# can2clusterV2.net
KiCad netlist of a schematic drawn in EasyEDA Pro
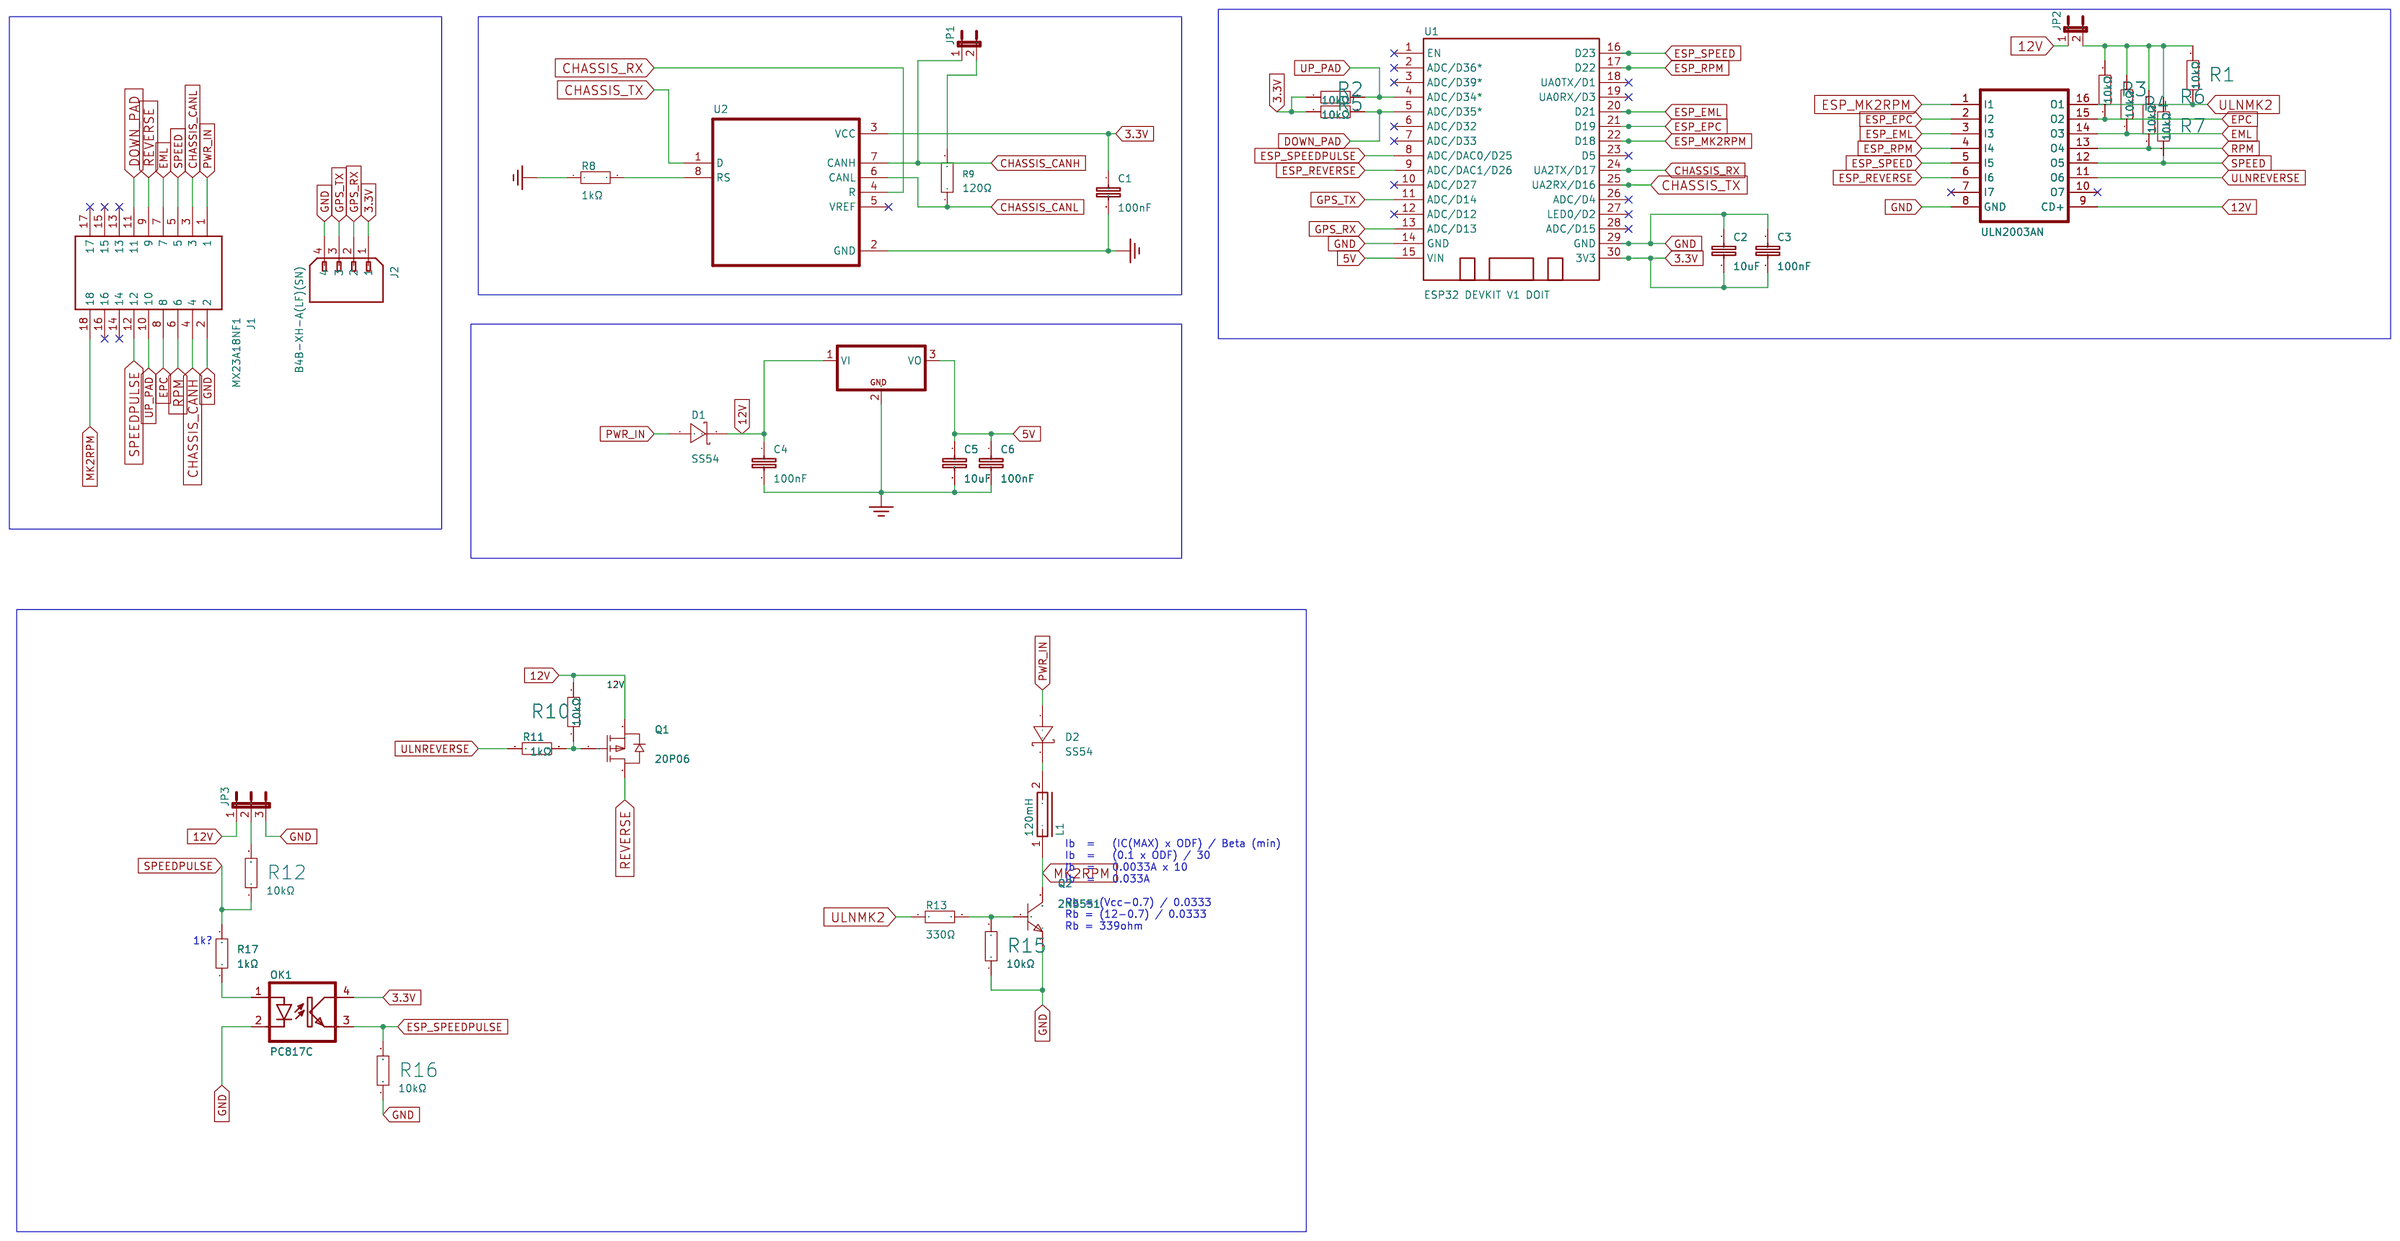
[diagram p0: schematic sheet]

(export (version "E")
  (design (tool "Eeschema 10.0.6"))
  (components
    (comp (ref "C1")
      (value "100nF")
      (footprint "easyedapro:C2.5-2")
      (description "Capacitance:100nF Tolerance:±10% Tolerance:±10% Voltage Rating:50V Temperature Coefficient:X7R")
      (fields
        (field (name "Manufacturer Part") "CC0603KRX7R9BB104")
        (field (name "Manufacturer") "YAGEO(国巨)")
      )
      (libsource (lib "easyedapro") (part "capacitor-wima_C_2.5/2"))
    )
    (comp (ref "C2")
      (value "10uF")
      (fields
        (field (name "Manufacturer Part") "CL21A106KAYNNNE")
        (field (name "Manufacturer") "SAMSUNG(三星)")
      )
      (libsource (lib "easyedapro") (part "capacitor-wima_C_2.5/2"))
    )
    (comp (ref "C3")
      (value "100nF")
      (footprint "easyedapro:C2.5-2")
      (description "Capacitance:100nF Tolerance:±10% Tolerance:±10% Voltage Rating:50V Temperature Coefficient:X7R")
      (fields
        (field (name "Manufacturer Part") "CC0603KRX7R9BB104")
        (field (name "Manufacturer") "YAGEO(国巨)")
      )
      (libsource (lib "easyedapro") (part "capacitor-wima_C_2.5/2"))
    )
    (comp (ref "C4")
      (value "100nF")
      (description "Capacitance:100nF Tolerance:±10% Tolerance:±10% Voltage Rating:50V Temperature Coefficient:X7R")
      (fields
        (field (name "Manufacturer Part") "CC0603KRX7R9BB104")
        (field (name "Manufacturer") "YAGEO(国巨)")
      )
      (libsource (lib "easyedapro") (part "capacitor-wima_C_2.5/2"))
    )
    (comp (ref "C5")
      (value "10uF")
      (fields
        (field (name "Manufacturer Part") "CL21A106KAYNNNE")
        (field (name "Manufacturer") "SAMSUNG(三星)")
      )
      (libsource (lib "easyedapro") (part "capacitor-wima_C_2.5/2"))
    )
    (comp (ref "C6")
      (value "100nF")
      (description "Capacitance:100nF Tolerance:±10% Tolerance:±10% Voltage Rating:50V Temperature Coefficient:X7R")
      (fields
        (field (name "Manufacturer Part") "CC0603KRX7R9BB104")
        (field (name "Manufacturer") "YAGEO(国巨)")
      )
      (libsource (lib "easyedapro") (part "capacitor-wima_C_2.5/2"))
    )
    (comp (ref "D1")
      (value "SS54")
      (footprint "easyedapro:SMA_L4.4-W2.8-LS5.4-R-RD")
      (fields (field (name "Manufacturer") "MDD(辰达半导体)"))
      (libsource (lib "easyedapro") (part "SS54_C22452"))
    )
    (comp (ref "D2")
      (value "SS54")
      (footprint "easyedapro:SMA_L4.4-W2.8-LS5.4-R-RD")
      (fields (field (name "Manufacturer") "MDD(辰达半导体)"))
      (libsource (lib "easyedapro") (part "SS54_C22452"))
    )
    (comp (ref "IC1")
      (value "ULN2003AN")
      (footprint "easyedapro:DIL16")
      (fields (field (name "Manufacturer") "HGSEMI(华冠)"))
      (libsource (lib "easyedapro") (part "ULN2003A_ULN2003A_N"))
    )
    (comp (ref "IC2")
      (value "L7805ABD2T-TR")
      (fields (field (name "Manufacturer") "ST(意法半导体)"))
      (libsource (lib "easyedapro") (part "linear_78*_TV"))
    )
    (comp (ref "J1")
      (value "MX23A18NF1")
      (footprint "easyedapro:MX23A18NF1")
      (fields (field (name "Manufacturer") "JAE(日本航空电子)"))
      (libsource (lib "easyedapro") (part "MX23A18NF1_MX23A18NF1_"))
    )
    (comp (ref "J2")
      (value "B4B-XH-A(LF)(SN)")
      (footprint "easyedapro:JST_B4B-XH-A(LF)(SN)")
      (fields (field (name "Manufacturer") "JST"))
      (libsource (lib "easyedapro") (part "B4B-XH-A_LF__SN__B4B-XH-A(LF)(SN)_"))
    )
    (comp (ref "JP1")
      (value "PZ254V-11-02P")
      (footprint "easyedapro:JP1")
      (fields (field (name "Manufacturer") "XFCN(兴飞)"))
      (libsource (lib "easyedapro") (part "jumper_JP1E_"))
    )
    (comp (ref "JP2")
      (value "PZ254V-11-02P")
      (footprint "easyedapro:JP1")
      (fields (field (name "Manufacturer") "XFCN(兴飞)"))
      (libsource (lib "easyedapro") (part "jumper_JP1E_"))
    )
    (comp (ref "JP3")
      (value "PZ254V-11-03P")
      (footprint "easyedapro:JP2")
      (fields (field (name "Manufacturer") "XFCN(兴飞)"))
      (libsource (lib "easyedapro") (part "jumper_JP2E_"))
    )
    (comp (ref "L1")
      (value "120mH")
      (footprint "easyedapro:DR125_3D")
      (fields (field (name "Manufacturer Part") "DR125-124-R") (field (name "Manufacturer") "EATON(伊顿)"))
      (libsource (lib "easyedapro") (part "DR125_DR125_"))
    )
    (comp (ref "OK1")
      (value "PC817C")
      (footprint "easyedapro:DIL04")
      (fields (field (name "Manufacturer") "GOODWORK(固得沃克)"))
      (libsource (lib "easyedapro") (part "optocoupler_PC817_"))
    )
    (comp (ref "Q1")
      (value "20P06")
      (footprint "easyedapro:TO-252-2_L6.6-W6.1-P4.57-LS9.9-BR-CW")
      (fields (field (name "Manufacturer") "HL(富海微)"))
      (libsource (lib "easyedapro") (part "20P06"))
    )
    (comp (ref "Q2")
      (value "2N5551")
      (footprint "easyedapro:SOT-23-3_L2.9-W1.4-P1.90-LS2.5-BR")
      (fields (field (name "Manufacturer") "RUILON(瑞隆源)"))
      (libsource (lib "easyedapro") (part "2N5551_C7529570"))
    )
    (comp (ref "R1")
      (value "10kΩ")
      (footprint "easyedapro:R0603")
      (fields
        (field (name "Manufacturer Part") "0603WAF1002T5E")
        (field (name "Manufacturer") "UNI-ROYAL(厚声)")
      )
      (libsource (lib "easyedapro") (part "0603WAF1002T5E"))
    )
    (comp (ref "R2")
      (value "10kΩ")
      (footprint "easyedapro:R0603")
      (fields
        (field (name "Manufacturer Part") "0603WAF1002T5E")
        (field (name "Manufacturer") "UNI-ROYAL(厚声)")
      )
      (libsource (lib "easyedapro") (part "0603WAF1002T5E"))
    )
    (comp (ref "R3")
      (value "10kΩ")
      (footprint "easyedapro:R0603")
      (fields
        (field (name "Manufacturer Part") "0603WAF1002T5E")
        (field (name "Manufacturer") "UNI-ROYAL(厚声)")
      )
      (libsource (lib "easyedapro") (part "0603WAF1002T5E"))
    )
    (comp (ref "R4")
      (value "10kΩ")
      (footprint "easyedapro:R0603")
      (fields
        (field (name "Manufacturer Part") "0603WAF1002T5E")
        (field (name "Manufacturer") "UNI-ROYAL(厚声)")
      )
      (libsource (lib "easyedapro") (part "0603WAF1002T5E"))
    )
    (comp (ref "R5")
      (value "10kΩ")
      (footprint "easyedapro:R0603")
      (fields
        (field (name "Manufacturer Part") "0603WAF1002T5E")
        (field (name "Manufacturer") "UNI-ROYAL(厚声)")
      )
      (libsource (lib "easyedapro") (part "0603WAF1002T5E"))
    )
    (comp (ref "R6")
      (value "10kΩ")
      (footprint "easyedapro:R0603")
      (fields
        (field (name "Manufacturer Part") "0603WAF1002T5E")
        (field (name "Manufacturer") "UNI-ROYAL(厚声)")
      )
      (libsource (lib "easyedapro") (part "0603WAF1002T5E"))
    )
    (comp (ref "R7")
      (value "10kΩ")
      (footprint "easyedapro:R0603")
      (fields
        (field (name "Manufacturer Part") "0603WAF1002T5E")
        (field (name "Manufacturer") "UNI-ROYAL(厚声)")
      )
      (libsource (lib "easyedapro") (part "0603WAF1002T5E"))
    )
    (comp (ref "R8")
      (value "1kΩ")
      (footprint "easyedapro:R0603")
      (fields
        (field (name "Manufacturer Part") "0603WAF1001T5E")
        (field (name "Manufacturer") "UNI-ROYAL(厚声)")
      )
      (libsource (lib "easyedapro") (part "0603WAF1001T5E"))
    )
    (comp (ref "R9")
      (value "120Ω")
      (footprint "easyedapro:R0603")
      (fields
        (field (name "Manufacturer Part") "0603WAF1200T5E")
        (field (name "Manufacturer") "UNI-ROYAL(厚声)")
      )
      (libsource (lib "easyedapro") (part "0603WAF1200T5E"))
    )
    (comp (ref "R10")
      (value "10kΩ")
      (footprint "easyedapro:R0603")
      (fields
        (field (name "Manufacturer Part") "0603WAF1002T5E")
        (field (name "Manufacturer") "UNI-ROYAL(厚声)")
      )
      (libsource (lib "easyedapro") (part "0603WAF1002T5E"))
    )
    (comp (ref "R11")
      (value "1kΩ")
      (footprint "easyedapro:R0603")
      (fields
        (field (name "Manufacturer Part") "0603WAF1001T5E")
        (field (name "Manufacturer") "UNI-ROYAL(厚声)")
      )
      (libsource (lib "easyedapro") (part "0603WAF1001T5E"))
    )
    (comp (ref "R12")
      (value "10kΩ")
      (footprint "easyedapro:R0603")
      (fields
        (field (name "Manufacturer Part") "0603WAF1002T5E")
        (field (name "Manufacturer") "UNI-ROYAL(厚声)")
      )
      (libsource (lib "easyedapro") (part "0603WAF1002T5E"))
    )
    (comp (ref "R13")
      (value "330Ω")
      (footprint "easyedapro:R0603")
      (fields
        (field (name "Manufacturer Part") "0603WAF3300T5E")
        (field (name "Manufacturer") "UNI-ROYAL(厚声)")
      )
      (libsource (lib "easyedapro") (part "0603WAF3300T5E"))
    )
    (comp (ref "R15")
      (value "10kΩ")
      (footprint "easyedapro:R0603")
      (fields
        (field (name "Manufacturer Part") "0603WAF1002T5E")
        (field (name "Manufacturer") "UNI-ROYAL(厚声)")
      )
      (libsource (lib "easyedapro") (part "0603WAF1002T5E"))
    )
    (comp (ref "R16")
      (value "10kΩ")
      (footprint "easyedapro:R0603")
      (fields
        (field (name "Manufacturer Part") "0603WAF1002T5E")
        (field (name "Manufacturer") "UNI-ROYAL(厚声)")
      )
      (libsource (lib "easyedapro") (part "0603WAF1002T5E"))
    )
    (comp (ref "R17")
      (value "1kΩ")
      (footprint "easyedapro:R0603")
      (fields
        (field (name "Manufacturer Part") "0603WAF1001T5E")
        (field (name "Manufacturer") "UNI-ROYAL(厚声)")
      )
      (libsource (lib "easyedapro") (part "0603WAF1001T5E"))
    )
    (comp (ref "U1")
      (value "ESP32 DEVKIT V1 DOIT")
      (footprint "easyedapro:DOIT-ESP32-DEVKIT-V1")
      (libsource (lib "easyedapro") (part "ESP32 DEVKIT V1 DOIT"))
    )
    (comp (ref "U2")
      (value "SN65HVD230DR")
      (footprint "easyedapro:SOIC127P599X175-8N")
      (fields (field (name "Manufacturer") "TI(德州仪器)"))
      (libsource (lib "easyedapro") (part "SN65HVD230DR_SN65HVD230DR_"))
    )
  )
  (nets
    (net (code "1") (name "3.3V") (class "Default")
      (node (ref "C1") (pin "1") (pinfunction "1_1") (pintype "unspecified"))
      (node (ref "C2") (pin "2") (pinfunction "2_2") (pintype "unspecified"))
      (node (ref "C3") (pin "2") (pinfunction "2_2") (pintype "unspecified"))
      (node (ref "J2") (pin "1") (pinfunction "1_1") (pintype "unspecified"))
      (node (ref "OK1") (pin "4") (pinfunction "COL_4") (pintype "unspecified"))
      (node (ref "R2") (pin "1") (pinfunction "1_1") (pintype "input"))
      (node (ref "R5") (pin "1") (pinfunction "1_1") (pintype "input"))
      (node (ref "U1") (pin "30") (pinfunction "3V3_30") (pintype "bidirectional"))
      (node (ref "U2") (pin "3") (pinfunction "VCC_3") (pintype "unspecified"))
    )
    (net (code "2") (name "5V") (class "Default")
      (node (ref "C5") (pin "1") (pinfunction "1_1") (pintype "unspecified"))
      (node (ref "C6") (pin "1") (pinfunction "1_1") (pintype "unspecified"))
      (node (ref "IC2") (pin "3") (pinfunction "VO_3") (pintype "unspecified"))
      (node (ref "U1") (pin "15") (pinfunction "VIN_15") (pintype "input"))
    )
    (net (code "3") (name "12V") (class "Default")
      (node (ref "C4") (pin "1") (pinfunction "1_1") (pintype "unspecified"))
      (node (ref "D1") (pin "2") (pinfunction "K_2") (pintype "unspecified"))
      (node (ref "IC1") (pin "9") (pinfunction "CD+_9") (pintype "unspecified"))
      (node (ref "IC2") (pin "1") (pinfunction "VI_1") (pintype "input"))
      (node (ref "JP2") (pin "1") (pinfunction "1_1") (pintype "unspecified"))
      (node (ref "JP3") (pin "1") (pinfunction "1_1") (pintype "unspecified"))
      (node (ref "Q1") (pin "3") (pinfunction "S_3") (pintype "unspecified"))
      (node (ref "R10") (pin "2") (pinfunction "2_2") (pintype "input"))
    )
    (net (code "4") (name "CHASSIS_CANH") (class "Default")
      (node (ref "J1") (pin "4") (pinfunction "4_4") (pintype "bidirectional"))
      (node (ref "JP1") (pin "1") (pinfunction "1_1") (pintype "unspecified"))
      (node (ref "U2") (pin "7") (pinfunction "CANH_7") (pintype "output"))
    )
    (net (code "5") (name "CHASSIS_CANL") (class "Default")
      (node (ref "J1") (pin "3") (pinfunction "3_3") (pintype "bidirectional"))
      (node (ref "R9") (pin "1") (pinfunction "1_1") (pintype "input"))
      (node (ref "U2") (pin "6") (pinfunction "CANL_6") (pintype "output"))
    )
    (net (code "6") (name "CHASSIS_RX") (class "Default")
      (node (ref "U1") (pin "24") (pinfunction "UA2TX/D17_24") (pintype "bidirectional"))
      (node (ref "U2") (pin "4") (pinfunction "R_4") (pintype "output"))
    )
    (net (code "7") (name "CHASSIS_TX") (class "Default")
      (node (ref "U1") (pin "25") (pinfunction "UA2RX/D16_25") (pintype "bidirectional"))
      (node (ref "U2") (pin "1") (pinfunction "D_1") (pintype "input"))
    )
    (net (code "8") (name "DOWN_PAD") (class "Default")
      (node (ref "J1") (pin "11") (pinfunction "11_11") (pintype "bidirectional"))
      (node (ref "R5") (pin "2") (pinfunction "2_2") (pintype "input"))
      (node (ref "U1") (pin "5") (pinfunction "ADC/D35*_5") (pintype "input"))
    )
    (net (code "9") (name "EML") (class "Default")
      (node (ref "IC1") (pin "14") (pinfunction "O3_14") (pintype "unspecified"))
      (node (ref "J1") (pin "7") (pinfunction "7_7") (pintype "bidirectional"))
      (node (ref "R4") (pin "1") (pinfunction "1_1") (pintype "input"))
    )
    (net (code "10") (name "EPC") (class "Default")
      (node (ref "IC1") (pin "15") (pinfunction "O2_15") (pintype "unspecified"))
      (node (ref "J1") (pin "8") (pinfunction "8_8") (pintype "bidirectional"))
      (node (ref "R3") (pin "1") (pinfunction "1_1") (pintype "input"))
    )
    (net (code "11") (name "ESP_EML") (class "Default")
      (node (ref "IC1") (pin "3") (pinfunction "I3_3") (pintype "input"))
      (node (ref "U1") (pin "20") (pinfunction "D21_20") (pintype "bidirectional"))
    )
    (net (code "12") (name "ESP_EPC") (class "Default")
      (node (ref "IC1") (pin "2") (pinfunction "I2_2") (pintype "input"))
      (node (ref "U1") (pin "21") (pinfunction "D19_21") (pintype "bidirectional"))
    )
    (net (code "13") (name "ESP_MK2RPM") (class "Default")
      (node (ref "IC1") (pin "1") (pinfunction "I1_1") (pintype "input"))
      (node (ref "U1") (pin "22") (pinfunction "D18_22") (pintype "bidirectional"))
    )
    (net (code "14") (name "ESP_REVERSE") (class "Default")
      (node (ref "IC1") (pin "6") (pinfunction "I6_6") (pintype "input"))
      (node (ref "U1") (pin "9") (pinfunction "ADC/DAC1/D26_9") (pintype "bidirectional"))
    )
    (net (code "15") (name "ESP_RPM") (class "Default")
      (node (ref "IC1") (pin "4") (pinfunction "I4_4") (pintype "input"))
      (node (ref "U1") (pin "17") (pinfunction "D22_17") (pintype "bidirectional"))
    )
    (net (code "16") (name "ESP_SPEED") (class "Default")
      (node (ref "IC1") (pin "5") (pinfunction "I5_5") (pintype "input"))
      (node (ref "U1") (pin "16") (pinfunction "D23_16") (pintype "bidirectional"))
    )
    (net (code "17") (name "ESP_SPEEDPULSE") (class "Default")
      (node (ref "OK1") (pin "3") (pinfunction "EMIT_3") (pintype "unspecified"))
      (node (ref "R16") (pin "2") (pinfunction "2_2") (pintype "input"))
      (node (ref "U1") (pin "8") (pinfunction "ADC/DAC0/D25_8") (pintype "bidirectional"))
    )
    (net (code "18") (name "GND") (class "Default")
      (node (ref "C1") (pin "2") (pinfunction "2_2") (pintype "unspecified"))
      (node (ref "C2") (pin "1") (pinfunction "1_1") (pintype "unspecified"))
      (node (ref "C3") (pin "1") (pinfunction "1_1") (pintype "unspecified"))
      (node (ref "C4") (pin "2") (pinfunction "2_2") (pintype "unspecified"))
      (node (ref "C5") (pin "2") (pinfunction "2_2") (pintype "unspecified"))
      (node (ref "C6") (pin "2") (pinfunction "2_2") (pintype "unspecified"))
      (node (ref "IC1") (pin "8") (pinfunction "GND_8") (pintype "unspecified"))
      (node (ref "IC2") (pin "2") (pinfunction "GND_2") (pintype "unspecified"))
      (node (ref "J1") (pin "2") (pinfunction "2_2") (pintype "bidirectional"))
      (node (ref "J2") (pin "4") (pinfunction "4_4") (pintype "unspecified"))
      (node (ref "JP3") (pin "3") (pinfunction "3_3") (pintype "unspecified"))
      (node (ref "OK1") (pin "2") (pinfunction "C_2") (pintype "unspecified"))
      (node (ref "Q2") (pin "2") (pinfunction "E_2") (pintype "unspecified"))
      (node (ref "R15") (pin "1") (pinfunction "1_1") (pintype "input"))
      (node (ref "R16") (pin "1") (pinfunction "1_1") (pintype "input"))
      (node (ref "R8") (pin "1") (pinfunction "1_1") (pintype "input"))
      (node (ref "U1") (pin "14") (pinfunction "GND_14") (pintype "bidirectional"))
      (node (ref "U1") (pin "29") (pinfunction "GND_29") (pintype "bidirectional"))
      (node (ref "U2") (pin "2") (pinfunction "GND_2") (pintype "unspecified"))
    )
    (net (code "19") (name "GPS_RX") (class "Default")
      (node (ref "J2") (pin "2") (pinfunction "2_2") (pintype "unspecified"))
      (node (ref "U1") (pin "13") (pinfunction "ADC/D13_13") (pintype "bidirectional"))
    )
    (net (code "20") (name "GPS_TX") (class "Default")
      (node (ref "J2") (pin "3") (pinfunction "3_3") (pintype "unspecified"))
      (node (ref "U1") (pin "11") (pinfunction "ADC/D14_11") (pintype "bidirectional"))
    )
    (net (code "21") (name "MK2RPM") (class "Default")
      (node (ref "J1") (pin "18") (pinfunction "18_18") (pintype "bidirectional"))
      (node (ref "L1") (pin "1") (pinfunction "1_1") (pintype "unspecified"))
      (node (ref "Q2") (pin "3") (pinfunction "C_3") (pintype "unspecified"))
    )
    (net (code "22") (name "Net-(D2-K)") (class "Default")
      (node (ref "D2") (pin "2") (pinfunction "K_2") (pintype "unspecified"))
      (node (ref "L1") (pin "2") (pinfunction "2_2") (pintype "unspecified"))
    )
    (net (code "23") (name "Net-(JP1-Pad2)") (class "Default")
      (node (ref "JP1") (pin "2") (pinfunction "2_2") (pintype "unspecified"))
      (node (ref "R9") (pin "2") (pinfunction "2_2") (pintype "input"))
    )
    (net (code "24") (name "Net-(JP2-Pad2)") (class "Default")
      (node (ref "JP2") (pin "2") (pinfunction "2_2") (pintype "unspecified"))
      (node (ref "R1") (pin "2") (pinfunction "2_2") (pintype "input"))
      (node (ref "R3") (pin "2") (pinfunction "2_2") (pintype "input"))
      (node (ref "R4") (pin "2") (pinfunction "2_2") (pintype "input"))
      (node (ref "R6") (pin "2") (pinfunction "2_2") (pintype "input"))
      (node (ref "R7") (pin "2") (pinfunction "2_2") (pintype "input"))
    )
    (net (code "25") (name "Net-(JP3-Pad2)") (class "Default")
      (node (ref "JP3") (pin "2") (pinfunction "2_2") (pintype "unspecified"))
      (node (ref "R12") (pin "2") (pinfunction "2_2") (pintype "input"))
    )
    (net (code "26") (name "Net-(OK1-A)") (class "Default")
      (node (ref "OK1") (pin "1") (pinfunction "A_1") (pintype "unspecified"))
      (node (ref "R17") (pin "1") (pinfunction "1_1") (pintype "input"))
    )
    (net (code "27") (name "Net-(Q1-G)") (class "Default")
      (node (ref "Q1") (pin "1") (pinfunction "G_1") (pintype "unspecified"))
      (node (ref "R10") (pin "1") (pinfunction "1_1") (pintype "input"))
      (node (ref "R11") (pin "2") (pinfunction "2_2") (pintype "input"))
    )
    (net (code "28") (name "Net-(Q2-B)") (class "Default")
      (node (ref "Q2") (pin "1") (pinfunction "B_1") (pintype "unspecified"))
      (node (ref "R13") (pin "2") (pinfunction "2_2") (pintype "input"))
      (node (ref "R15") (pin "2") (pinfunction "2_2") (pintype "input"))
    )
    (net (code "29") (name "Net-(U2-RS)") (class "Default")
      (node (ref "R8") (pin "2") (pinfunction "2_2") (pintype "input"))
      (node (ref "U2") (pin "8") (pinfunction "RS_8") (pintype "input"))
    )
    (net (code "30") (name "PWR_IN") (class "Default")
      (node (ref "D1") (pin "1") (pinfunction "A_1") (pintype "unspecified"))
      (node (ref "D2") (pin "1") (pinfunction "A_1") (pintype "unspecified"))
      (node (ref "J1") (pin "1") (pinfunction "1_1") (pintype "bidirectional"))
    )
    (net (code "31") (name "REVERSE") (class "Default")
      (node (ref "J1") (pin "9") (pinfunction "9_9") (pintype "bidirectional"))
      (node (ref "Q1") (pin "2") (pinfunction "D_2") (pintype "unspecified"))
    )
    (net (code "32") (name "RPM") (class "Default")
      (node (ref "IC1") (pin "13") (pinfunction "O4_13") (pintype "unspecified"))
      (node (ref "J1") (pin "6") (pinfunction "6_6") (pintype "bidirectional"))
      (node (ref "R6") (pin "1") (pinfunction "1_1") (pintype "input"))
    )
    (net (code "33") (name "SPEED") (class "Default")
      (node (ref "IC1") (pin "12") (pinfunction "O5_12") (pintype "unspecified"))
      (node (ref "J1") (pin "5") (pinfunction "5_5") (pintype "bidirectional"))
      (node (ref "R7") (pin "1") (pinfunction "1_1") (pintype "input"))
    )
    (net (code "34") (name "SPEEDPULSE") (class "Default")
      (node (ref "J1") (pin "12") (pinfunction "12_12") (pintype "bidirectional"))
      (node (ref "R12") (pin "1") (pinfunction "1_1") (pintype "input"))
      (node (ref "R17") (pin "2") (pinfunction "2_2") (pintype "input"))
    )
    (net (code "35") (name "ULNMK2") (class "Default")
      (node (ref "IC1") (pin "16") (pinfunction "O1_16") (pintype "unspecified"))
      (node (ref "R1") (pin "1") (pinfunction "1_1") (pintype "input"))
      (node (ref "R13") (pin "1") (pinfunction "1_1") (pintype "input"))
    )
    (net (code "36") (name "ULNREVERSE") (class "Default")
      (node (ref "IC1") (pin "11") (pinfunction "O6_11") (pintype "unspecified"))
      (node (ref "R11") (pin "1") (pinfunction "1_1") (pintype "input"))
    )
    (net (code "37") (name "UP_PAD") (class "Default")
      (node (ref "J1") (pin "10") (pinfunction "10_10") (pintype "bidirectional"))
      (node (ref "R2") (pin "2") (pinfunction "2_2") (pintype "input"))
      (node (ref "U1") (pin "4") (pinfunction "ADC/D34*_4") (pintype "input"))
    )
    (net (code "38") (name "unconnected-(IC1-I7-Pad7)") (class "Default")
      (node (ref "IC1") (pin "7") (pinfunction "I7_7") (pintype "input+no_connect"))
    )
    (net (code "39") (name "unconnected-(IC1-O7-Pad10)") (class "Default")
      (node (ref "IC1") (pin "10") (pinfunction "O7_10") (pintype "unspecified+no_connect"))
    )
    (net (code "40") (name "unconnected-(J1-Pad13)") (class "Default")
      (node (ref "J1") (pin "13") (pinfunction "13_13") (pintype "bidirectional+no_connect"))
    )
    (net (code "41") (name "unconnected-(J1-Pad14)") (class "Default")
      (node (ref "J1") (pin "14") (pinfunction "14_14") (pintype "bidirectional+no_connect"))
    )
    (net (code "42") (name "unconnected-(J1-Pad15)") (class "Default")
      (node (ref "J1") (pin "15") (pinfunction "15_15") (pintype "bidirectional+no_connect"))
    )
    (net (code "43") (name "unconnected-(J1-Pad16)") (class "Default")
      (node (ref "J1") (pin "16") (pinfunction "16_16") (pintype "bidirectional+no_connect"))
    )
    (net (code "44") (name "unconnected-(J1-Pad17)") (class "Default")
      (node (ref "J1") (pin "17") (pinfunction "17_17") (pintype "bidirectional+no_connect"))
    )
    (net (code "45") (name "unconnected-(U1-ADC{slash}D4-Pad26)") (class "Default")
      (node (ref "U1") (pin "26") (pinfunction "ADC/D4_26") (pintype "bidirectional+no_connect"))
    )
    (net (code "46") (name "unconnected-(U1-ADC{slash}D12-Pad12)") (class "Default")
      (node (ref "U1") (pin "12") (pinfunction "ADC/D12_12") (pintype "bidirectional+no_connect"))
    )
    (net (code "47") (name "unconnected-(U1-ADC{slash}D15-Pad28)") (class "Default")
      (node (ref "U1") (pin "28") (pinfunction "ADC/D15_28") (pintype "bidirectional+no_connect"))
    )
    (net (code "48") (name "unconnected-(U1-ADC{slash}D27-Pad10)") (class "Default")
      (node (ref "U1") (pin "10") (pinfunction "ADC/D27_10") (pintype "bidirectional+no_connect"))
    )
    (net (code "49") (name "unconnected-(U1-ADC{slash}D32-Pad6)") (class "Default")
      (node (ref "U1") (pin "6") (pinfunction "ADC/D32_6") (pintype "bidirectional+no_connect"))
    )
    (net (code "50") (name "unconnected-(U1-ADC{slash}D33-Pad7)") (class "Default")
      (node (ref "U1") (pin "7") (pinfunction "ADC/D33_7") (pintype "bidirectional+no_connect"))
    )
    (net (code "51") (name "unconnected-(U1-ADC{slash}D36*-Pad2)") (class "Default")
      (node (ref "U1") (pin "2") (pinfunction "ADC/D36*_2") (pintype "input+no_connect"))
    )
    (net (code "52") (name "unconnected-(U1-ADC{slash}D39*-Pad3)") (class "Default")
      (node (ref "U1") (pin "3") (pinfunction "ADC/D39*_3") (pintype "input+no_connect"))
    )
    (net (code "53") (name "unconnected-(U1-D5-Pad23)") (class "Default")
      (node (ref "U1") (pin "23") (pinfunction "D5_23") (pintype "bidirectional+no_connect"))
    )
    (net (code "54") (name "unconnected-(U1-EN-Pad1)") (class "Default")
      (node (ref "U1") (pin "1") (pinfunction "EN_1") (pintype "bidirectional+no_connect"))
    )
    (net (code "55") (name "unconnected-(U1-LED0{slash}D2-Pad27)") (class "Default")
      (node (ref "U1") (pin "27") (pinfunction "LED0/D2_27") (pintype "bidirectional+no_connect"))
    )
    (net (code "56") (name "unconnected-(U1-UA0RX{slash}D3-Pad19)") (class "Default")
      (node (ref "U1") (pin "19") (pinfunction "UA0RX/D3_19") (pintype "bidirectional+no_connect"))
    )
    (net (code "57") (name "unconnected-(U1-UA0TX{slash}D1-Pad18)") (class "Default")
      (node (ref "U1") (pin "18") (pinfunction "UA0TX/D1_18") (pintype "bidirectional+no_connect"))
    )
    (net (code "58") (name "unconnected-(U2-VREF-Pad5)") (class "Default")
      (node (ref "U2") (pin "5") (pinfunction "VREF_5") (pintype "output+no_connect"))
    )
  )
)
